# 3-2.net
KiCad netlist of a schematic drawn in Altium Designer
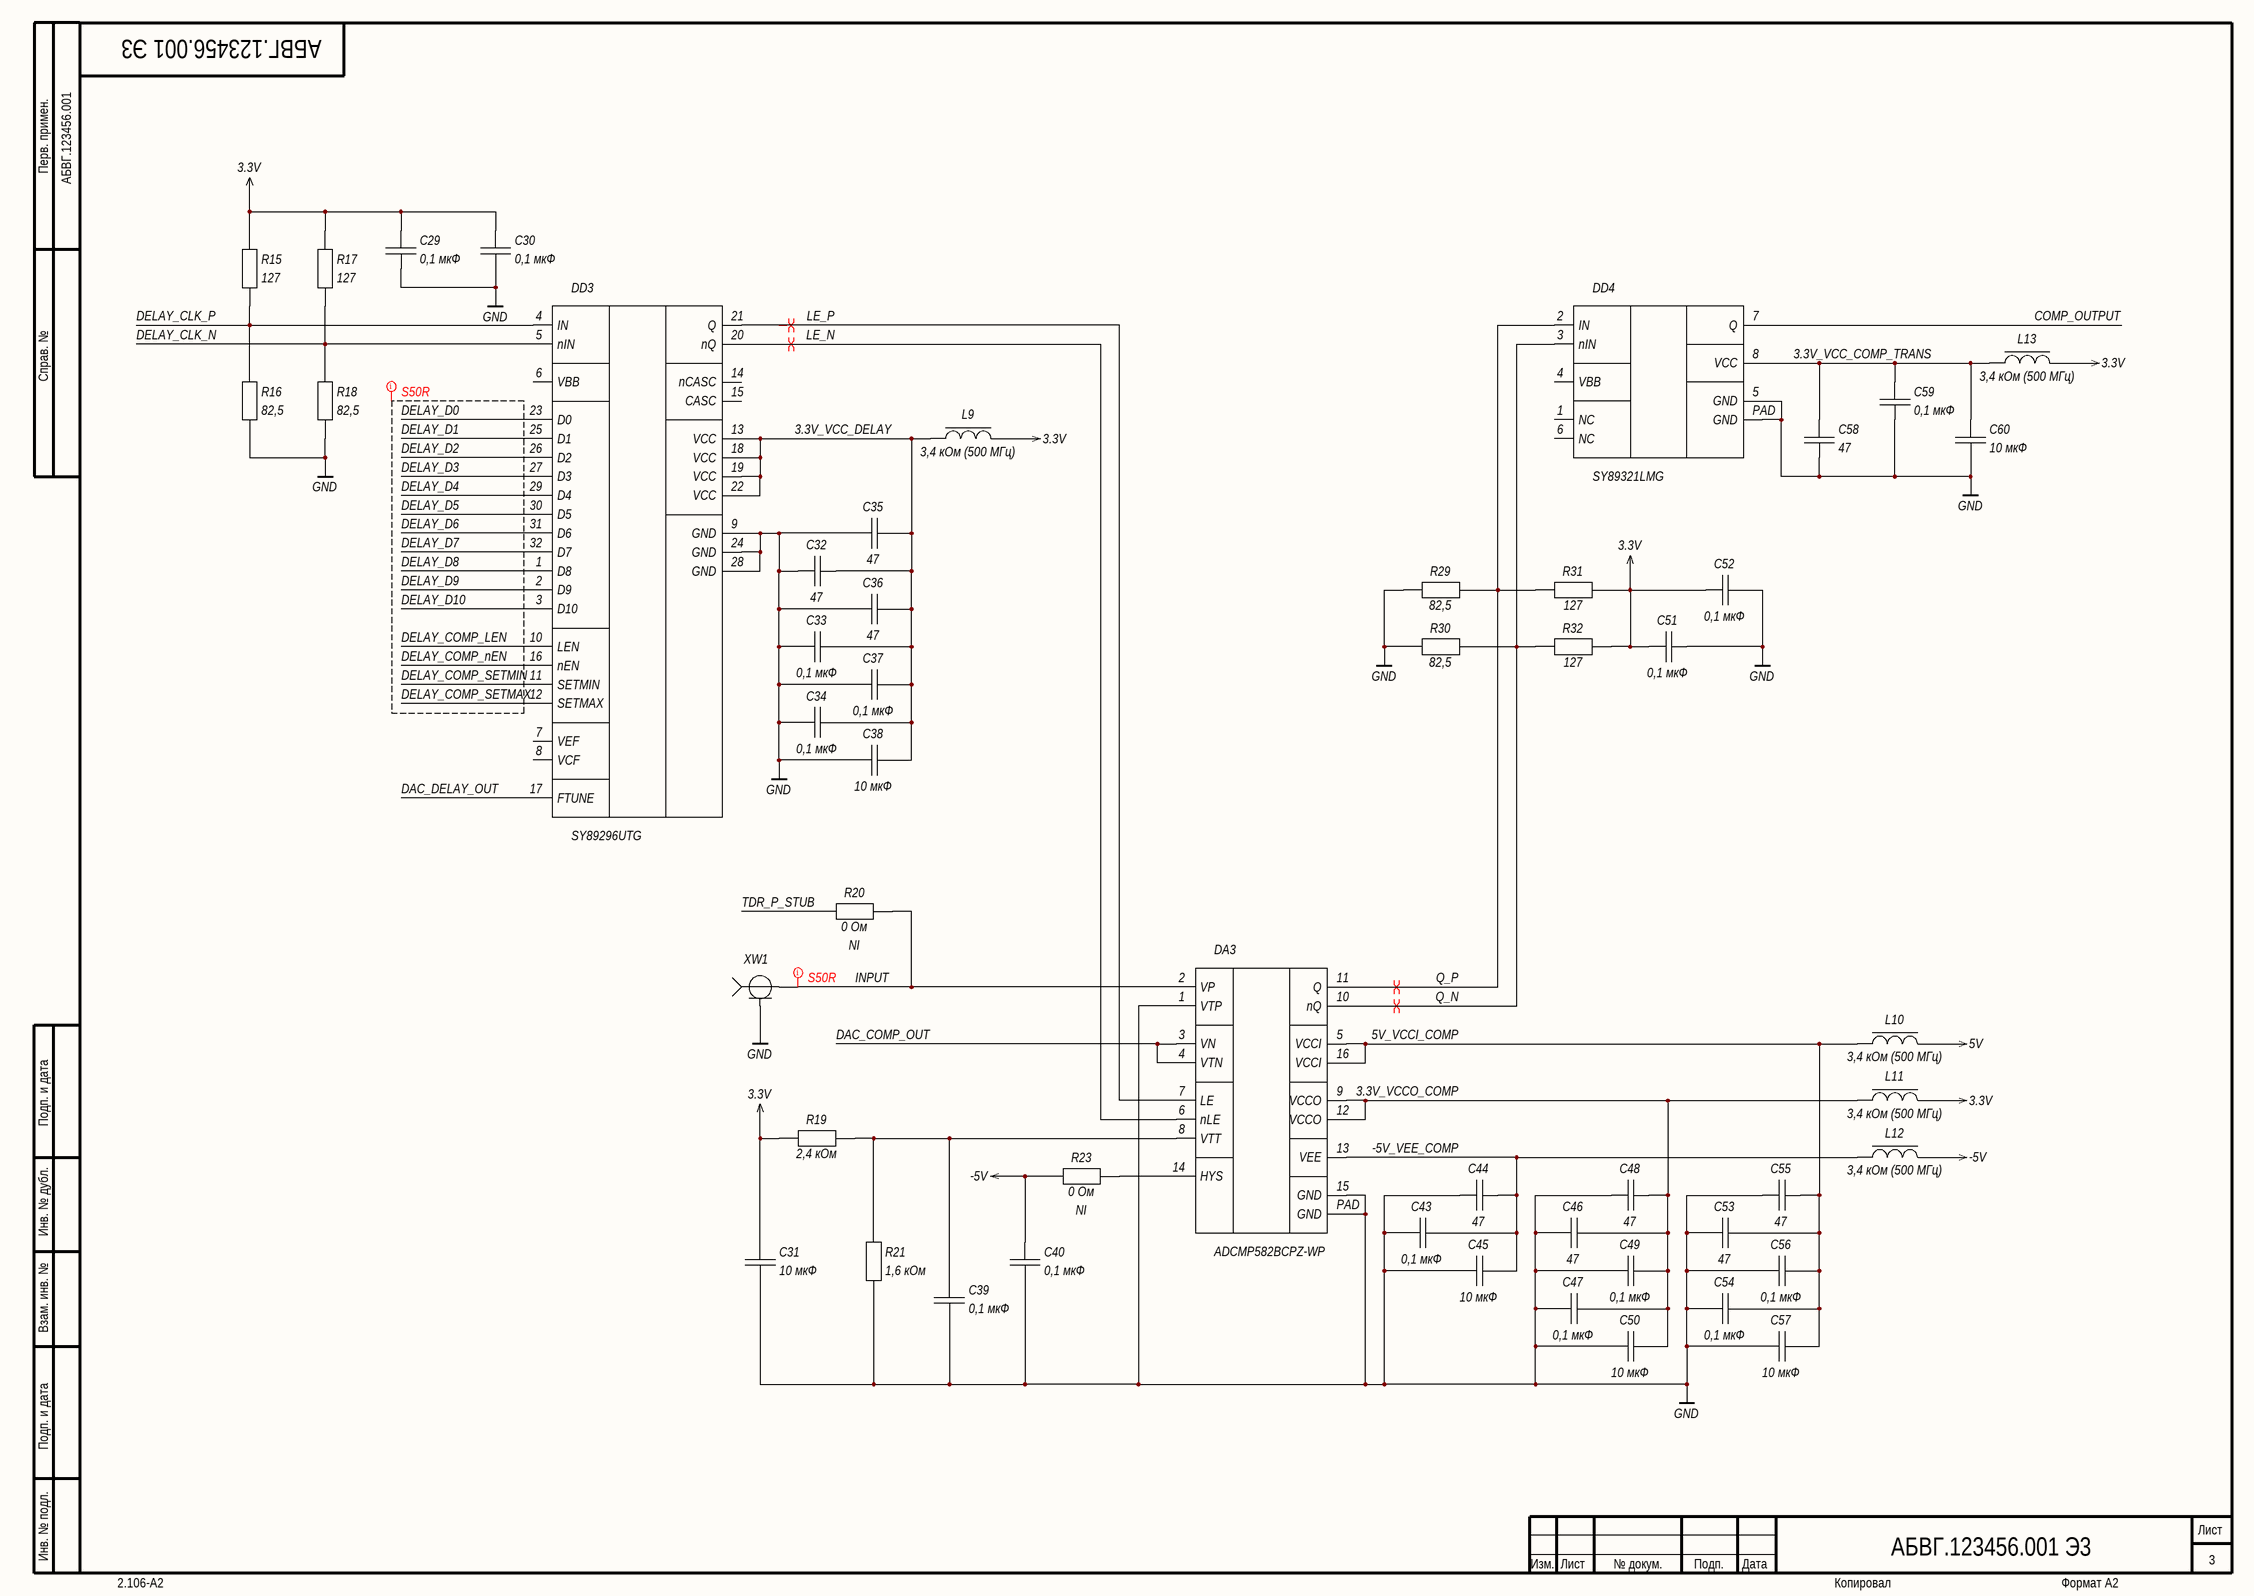
[diagram p0: Э3-2 УВ Компаратор.SchDoc]

(export (version "E")
  (design (tool "Eeschema 10.0.6"))
  (components
    (comp (ref "C29")
      (value "0,1 мкФ")
      (footprint "C0402-B-0.5mm")
      (description "0402 X7R 0,1 мкФ ±10 % 50 В")
      (fields (field (name "PARTNUMBER") "GRM155R71H104KE14D"))
      (libsource (lib "Capacitors") (part "Non Polar Ver."))
    )
    (comp (ref "C30")
      (value "0,1 мкФ")
      (footprint "C0402-B-0.5mm")
      (description "0402 X7R 0,1 мкФ ±10 % 50 В")
      (fields (field (name "PARTNUMBER") "GRM155R71H104KE14D"))
      (libsource (lib "Capacitors") (part "Non Polar Ver."))
    )
    (comp (ref "C31")
      (value "10 мкФ")
      (footprint "C0603-B-0.8mm")
      (description "0603 X5R 10 мкФ ±20 % 25 В")
      (fields (field (name "PARTNUMBER") "GRM188R61E106MA73"))
      (libsource (lib "Capacitors") (part "Non Polar Ver."))
    )
    (comp (ref "C32")
      (value "47")
      (footprint "C0402-B-0.5mm")
      (description "0402 NP0 47 пФ ±5 % 50 В")
      (fields (field (name "PARTNUMBER") "GCM1555C1H470JA16"))
      (libsource (lib "Capacitors") (part "Non Polar Hor."))
    )
    (comp (ref "C33")
      (value "0,1 мкФ")
      (footprint "C0402-B-0.5mm")
      (description "0402 X7R 0,1 мкФ ±10 % 50 В")
      (fields (field (name "PARTNUMBER") "GRM155R71H104KE14D"))
      (libsource (lib "Capacitors") (part "Non Polar Hor."))
    )
    (comp (ref "C34")
      (value "0,1 мкФ")
      (footprint "C0402-B-0.5mm")
      (description "0402 X7R 0,1 мкФ ±10 % 50 В")
      (fields (field (name "PARTNUMBER") "GRM155R71H104KE14D"))
      (libsource (lib "Capacitors") (part "Non Polar Hor."))
    )
    (comp (ref "C35")
      (value "47")
      (footprint "C0402-B-0.5mm")
      (description "0402 NP0 47 пФ ±5 % 50 В")
      (fields (field (name "PARTNUMBER") "GCM1555C1H470JA16"))
      (libsource (lib "Capacitors") (part "Non Polar Hor."))
    )
    (comp (ref "C36")
      (value "47")
      (footprint "C0402-B-0.5mm")
      (description "0402 NP0 47 пФ ±5 % 50 В")
      (fields (field (name "PARTNUMBER") "GCM1555C1H470JA16"))
      (libsource (lib "Capacitors") (part "Non Polar Hor."))
    )
    (comp (ref "C37")
      (value "0,1 мкФ")
      (footprint "C0402-B-0.5mm")
      (description "0402 X7R 0,1 мкФ ±10 % 50 В")
      (fields (field (name "PARTNUMBER") "GRM155R71H104KE14D"))
      (libsource (lib "Capacitors") (part "Non Polar Hor."))
    )
    (comp (ref "C38")
      (value "10 мкФ")
      (footprint "C0603-B-0.8mm")
      (description "0603 X5R 10 мкФ ±20 % 25 В")
      (fields (field (name "PARTNUMBER") "GRM188R61E106MA73"))
      (libsource (lib "Capacitors") (part "Non Polar Hor."))
    )
    (comp (ref "C39")
      (value "0,1 мкФ")
      (footprint "C0402-B-0.5mm")
      (description "0402 X7R 0,1 мкФ ±10 % 50 В")
      (fields (field (name "PARTNUMBER") "GRM155R71H104KE14D"))
      (libsource (lib "Capacitors") (part "Non Polar Ver."))
    )
    (comp (ref "C40")
      (value "0,1 мкФ")
      (footprint "C0402-B-0.5mm")
      (description "0402 X7R 0,1 мкФ ±10 % 50 В")
      (fields (field (name "PARTNUMBER") "GRM155R71H104KE14D"))
      (libsource (lib "Capacitors") (part "Non Polar Ver."))
    )
    (comp (ref "C43")
      (value "0,1 мкФ")
      (footprint "C0402-B-0.5mm")
      (description "0402 X7R 0,1 мкФ ±10 % 50 В")
      (fields (field (name "PARTNUMBER") "GRM155R71H104KE14D"))
      (libsource (lib "Capacitors") (part "Non Polar Hor."))
    )
    (comp (ref "C44")
      (value "47")
      (footprint "C0402-B-0.5mm")
      (description "0402 NP0 47 пФ ±5 % 50 В")
      (fields (field (name "PARTNUMBER") "GCM1555C1H470JA16"))
      (libsource (lib "Capacitors") (part "Non Polar Hor."))
    )
    (comp (ref "C45")
      (value "10 мкФ")
      (footprint "C0603-B-0.8mm")
      (description "0603 X5R 10 мкФ ±20 % 25 В")
      (fields (field (name "PARTNUMBER") "GRM188R61E106MA73"))
      (libsource (lib "Capacitors") (part "Non Polar Hor."))
    )
    (comp (ref "C46")
      (value "47")
      (footprint "C0402-B-0.5mm")
      (description "0402 NP0 47 пФ ±5 % 50 В")
      (fields (field (name "PARTNUMBER") "GCM1555C1H470JA16"))
      (libsource (lib "Capacitors") (part "Non Polar Hor."))
    )
    (comp (ref "C47")
      (value "0,1 мкФ")
      (footprint "C0402-B-0.5mm")
      (description "0402 X7R 0,1 мкФ ±10 % 50 В")
      (fields (field (name "PARTNUMBER") "GRM155R71H104KE14D"))
      (libsource (lib "Capacitors") (part "Non Polar Hor."))
    )
    (comp (ref "C48")
      (value "47")
      (footprint "C0402-B-0.5mm")
      (description "0402 NP0 47 пФ ±5 % 50 В")
      (fields (field (name "PARTNUMBER") "GCM1555C1H470JA16"))
      (libsource (lib "Capacitors") (part "Non Polar Hor."))
    )
    (comp (ref "C49")
      (value "0,1 мкФ")
      (footprint "C0402-B-0.5mm")
      (description "0402 X7R 0,1 мкФ ±10 % 50 В")
      (fields (field (name "PARTNUMBER") "GRM155R71H104KE14D"))
      (libsource (lib "Capacitors") (part "Non Polar Hor."))
    )
    (comp (ref "C50")
      (value "10 мкФ")
      (footprint "C0603-B-0.8mm")
      (description "0603 X5R 10 мкФ ±20 % 25 В")
      (fields (field (name "PARTNUMBER") "GRM188R61E106MA73"))
      (libsource (lib "Capacitors") (part "Non Polar Hor."))
    )
    (comp (ref "C51")
      (value "0,1 мкФ")
      (footprint "C0402-B-0.5mm")
      (description "0402 X7R 0,1 мкФ ±10 % 50 В")
      (fields (field (name "PARTNUMBER") "GRM155R71H104KE14D"))
      (libsource (lib "Capacitors") (part "Non Polar Hor."))
    )
    (comp (ref "C52")
      (value "0,1 мкФ")
      (footprint "C0402-B-0.5mm")
      (description "0402 X7R 0,1 мкФ ±10 % 50 В")
      (fields (field (name "PARTNUMBER") "GRM155R71H104KE14D"))
      (libsource (lib "Capacitors") (part "Non Polar Hor."))
    )
    (comp (ref "C53")
      (value "47")
      (footprint "C0402-B-0.5mm")
      (description "0402 NP0 47 пФ ±5 % 50 В")
      (fields (field (name "PARTNUMBER") "GCM1555C1H470JA16"))
      (libsource (lib "Capacitors") (part "Non Polar Hor."))
    )
    (comp (ref "C54")
      (value "0,1 мкФ")
      (footprint "C0402-B-0.5mm")
      (description "0402 X7R 0,1 мкФ ±10 % 50 В")
      (fields (field (name "PARTNUMBER") "GRM155R71H104KE14D"))
      (libsource (lib "Capacitors") (part "Non Polar Hor."))
    )
    (comp (ref "C55")
      (value "47")
      (footprint "C0402-B-0.5mm")
      (description "0402 NP0 47 пФ ±5 % 50 В")
      (fields (field (name "PARTNUMBER") "GCM1555C1H470JA16"))
      (libsource (lib "Capacitors") (part "Non Polar Hor."))
    )
    (comp (ref "C56")
      (value "0,1 мкФ")
      (footprint "C0402-B-0.5mm")
      (description "0402 X7R 0,1 мкФ ±10 % 50 В")
      (fields (field (name "PARTNUMBER") "GRM155R71H104KE14D"))
      (libsource (lib "Capacitors") (part "Non Polar Hor."))
    )
    (comp (ref "C57")
      (value "10 мкФ")
      (footprint "C0603-B-0.8mm")
      (description "0603 X5R 10 мкФ ±20 % 25 В")
      (fields (field (name "PARTNUMBER") "GRM188R61E106MA73"))
      (libsource (lib "Capacitors") (part "Non Polar Hor."))
    )
    (comp (ref "C58")
      (value "47")
      (footprint "C0402-B-0.5mm")
      (description "0402 NP0 47 пФ ±5 % 50 В")
      (fields (field (name "PARTNUMBER") "GCM1555C1H470JA16"))
      (libsource (lib "Capacitors") (part "Non Polar Ver."))
    )
    (comp (ref "C59")
      (value "0,1 мкФ")
      (footprint "C0402-B-0.5mm")
      (description "0402 X7R 0,1 мкФ ±10 % 50 В")
      (fields (field (name "PARTNUMBER") "GRM155R71H104KE14D"))
      (libsource (lib "Capacitors") (part "Non Polar Ver."))
    )
    (comp (ref "C60")
      (value "10 мкФ")
      (footprint "C0603-B-0.8mm")
      (description "0603 X5R 10 мкФ ±20 % 25 В")
      (fields (field (name "PARTNUMBER") "GRM188R61E106MA73"))
      (libsource (lib "Capacitors") (part "Non Polar Ver."))
    )
    (comp (ref "DA3")
      (value "ADCMP582BCPZ-WP")
      (footprint "16-LFCSP-3-H0.75")
      (description "Ultrafast SiGe Voltage Comparators")
      (fields (field (name "MANUFACTURER") "Analog Devices, Inc."))
      (libsource (lib "Analog") (part "ADCMP582"))
    )
    (comp (ref "DD3")
      (value "SY89296UTG")
      (footprint "32-TQFP-B")
      (description "2.5V/3.3V, 1.5 GHz, LVPECL Programmable Delay with Fine Tune Control")
      (fields (field (name "MANUFACTURER") "Microchip"))
      (libsource (lib "Digital") (part "SY89296UTG"))
    )
    (comp (ref "DD4")
      (value "SY89321LMG")
      (footprint "8-MLF")
      (description "3.3V DIFFERENTIAL LVPECL/CML/LVDS-to-LVTTL TRANSLATOR")
      (fields (field (name "MANUFACTURER") "Microchip Technology"))
      (libsource (lib "Digital") (part "SY89321L"))
    )
    (comp (ref "L9")
      (value "3,4 кОм (500 МГц)")
      (footprint "L0402-B-0.5mm")
      (fields (field (name "PARTNUMBER") "BLM15HD182BH1"))
      (libsource (lib "Inductors") (part "Inductor MC Hor."))
    )
    (comp (ref "L10")
      (value "3,4 кОм (500 МГц)")
      (footprint "L0402-B-0.5mm")
      (fields (field (name "PARTNUMBER") "BLM15HD182BH1"))
      (libsource (lib "Inductors") (part "Inductor MC Hor."))
    )
    (comp (ref "L11")
      (value "3,4 кОм (500 МГц)")
      (footprint "L0402-B-0.5mm")
      (fields (field (name "PARTNUMBER") "BLM15HD182BH1"))
      (libsource (lib "Inductors") (part "Inductor MC Hor."))
    )
    (comp (ref "L12")
      (value "3,4 кОм (500 МГц)")
      (footprint "L0402-B-0.5mm")
      (fields (field (name "PARTNUMBER") "BLM15HD182BH1"))
      (libsource (lib "Inductors") (part "Inductor MC Hor."))
    )
    (comp (ref "L13")
      (value "3,4 кОм (500 МГц)")
      (footprint "L0402-B-0.5mm")
      (fields (field (name "PARTNUMBER") "BLM15HD182BH1"))
      (libsource (lib "Inductors") (part "Inductor MC Hor."))
    )
    (comp (ref "R15")
      (value "127")
      (footprint "CR0402-B-0.35mm")
      (description "0402 127 Ом ±1 %")
      (libsource (lib "Resistors") (part "Resistor Ver."))
    )
    (comp (ref "R16")
      (value "82,5")
      (footprint "CR0402-B-0.35mm")
      (description "0402 82,5 Ом ±1 %")
      (libsource (lib "Resistors") (part "Resistor Ver."))
    )
    (comp (ref "R17")
      (value "127")
      (footprint "CR0402-B-0.35mm")
      (description "0402 127 Ом ±1 %")
      (libsource (lib "Resistors") (part "Resistor Ver."))
    )
    (comp (ref "R18")
      (value "82,5")
      (footprint "CR0402-B-0.35mm")
      (description "0402 82,5 Ом ±1 %")
      (libsource (lib "Resistors") (part "Resistor Ver."))
    )
    (comp (ref "R19")
      (value "2,4 кОм")
      (footprint "CR0402-B-0.35mm")
      (description "0402 2,4 кОм ±1 %")
      (libsource (lib "Resistors") (part "Resistor Hor."))
    )
    (comp (ref "R20")
      (value "0 Ом")
      (footprint "CR0402-B-0.35mm")
      (description "0402 0 Ом")
      (fields (field (name "COMPONENTTYPE") "NI"))
      (libsource (lib "") (part "Resistor Hor._1"))
    )
    (comp (ref "R21")
      (value "1,6 кОм")
      (footprint "CR0402-B-0.35mm")
      (description "0402 1,6 кОм ±1 %")
      (libsource (lib "Resistors") (part "Resistor Ver."))
    )
    (comp (ref "R23")
      (value "0 Ом")
      (footprint "CR0402-B-0.35mm")
      (description "0402 0 Ом")
      (fields (field (name "COMPONENTTYPE") "NI"))
      (libsource (lib "Resistors") (part "Resistor Hor."))
    )
    (comp (ref "R29")
      (value "82,5")
      (footprint "CR0402-B-0.35mm")
      (description "0402 82,5 Ом ±1 %")
      (libsource (lib "Resistors") (part "Resistor Hor."))
    )
    (comp (ref "R30")
      (value "82,5")
      (footprint "CR0402-B-0.35mm")
      (description "0402 82,5 Ом ±1 %")
      (libsource (lib "Resistors") (part "Resistor Hor."))
    )
    (comp (ref "R31")
      (value "127")
      (footprint "CR0402-B-0.35mm")
      (description "0402 127 Ом ±1 %")
      (libsource (lib "Resistors") (part "Resistor Hor."))
    )
    (comp (ref "R32")
      (value "127")
      (footprint "CR0402-B-0.35mm")
      (description "0402 127 Ом ±1 %")
      (libsource (lib "Resistors") (part "Resistor Hor."))
    )
    (comp (ref "XW1")
      (value "XW(S)")
      (footprint "SMA-J-P-H-ST-EM1")
      (libsource (lib "Connectors") (part "XW(S)"))
    )
  )
  (nets
    (net (code "1") (name "-5V") (class "Default")
      (node (ref "C40") (pin "1") (pinfunction "1_1") (pintype "passive"))
      (node (ref "L12") (pin "2") (pinfunction "2_2") (pintype "passive"))
      (node (ref "R23") (pin "1") (pinfunction "1_1") (pintype "passive"))
    )
    (net (code "2") (name "/-5V_VEE_COMP") (class "Default")
      (node (ref "C43") (pin "2") (pinfunction "2_2") (pintype "passive"))
      (node (ref "C44") (pin "2") (pinfunction "2_2") (pintype "passive"))
      (node (ref "C45") (pin "2") (pinfunction "2_2") (pintype "passive"))
      (node (ref "DA3") (pin "13") (pinfunction "VEE_13") (pintype "passive"))
      (node (ref "L12") (pin "1") (pinfunction "1_1") (pintype "passive"))
    )
    (net (code "3") (name "/3.3V_VCCO_COMP") (class "Default")
      (node (ref "C46") (pin "2") (pinfunction "2_2") (pintype "passive"))
      (node (ref "C47") (pin "2") (pinfunction "2_2") (pintype "passive"))
      (node (ref "C48") (pin "2") (pinfunction "2_2") (pintype "passive"))
      (node (ref "C49") (pin "2") (pinfunction "2_2") (pintype "passive"))
      (node (ref "C50") (pin "2") (pinfunction "2_2") (pintype "passive"))
      (node (ref "DA3") (pin "12") (pinfunction "VCCO_12") (pintype "passive"))
      (node (ref "DA3") (pin "9") (pinfunction "VCCO_9") (pintype "passive"))
      (node (ref "L11") (pin "1") (pinfunction "1_1") (pintype "passive"))
    )
    (net (code "4") (name "/3.3V_VCC_COMP_TRANS") (class "Default")
      (node (ref "C58") (pin "1") (pinfunction "1_1") (pintype "passive"))
      (node (ref "C59") (pin "1") (pinfunction "1_1") (pintype "passive"))
      (node (ref "C60") (pin "1") (pinfunction "1_1") (pintype "passive"))
      (node (ref "DD4") (pin "8") (pinfunction "VCC_8") (pintype "passive"))
      (node (ref "L13") (pin "1") (pinfunction "1_1") (pintype "passive"))
    )
    (net (code "5") (name "/3.3V_VCC_DELAY") (class "Default")
      (node (ref "C32") (pin "2") (pinfunction "2_2") (pintype "passive"))
      (node (ref "C33") (pin "2") (pinfunction "2_2") (pintype "passive"))
      (node (ref "C34") (pin "2") (pinfunction "2_2") (pintype "passive"))
      (node (ref "C35") (pin "2") (pinfunction "2_2") (pintype "passive"))
      (node (ref "C36") (pin "2") (pinfunction "2_2") (pintype "passive"))
      (node (ref "C37") (pin "2") (pinfunction "2_2") (pintype "passive"))
      (node (ref "C38") (pin "2") (pinfunction "2_2") (pintype "passive"))
      (node (ref "DD3") (pin "13") (pinfunction "VCC_13") (pintype "passive"))
      (node (ref "DD3") (pin "18") (pinfunction "VCC_18") (pintype "passive"))
      (node (ref "DD3") (pin "19") (pinfunction "VCC_19") (pintype "passive"))
      (node (ref "DD3") (pin "22") (pinfunction "VCC_22") (pintype "passive"))
      (node (ref "L9") (pin "1") (pinfunction "1_1") (pintype "passive"))
    )
    (net (code "6") (name "/5V_VCCI_COMP") (class "Default")
      (node (ref "C53") (pin "2") (pinfunction "2_2") (pintype "passive"))
      (node (ref "C54") (pin "2") (pinfunction "2_2") (pintype "passive"))
      (node (ref "C55") (pin "2") (pinfunction "2_2") (pintype "passive"))
      (node (ref "C56") (pin "2") (pinfunction "2_2") (pintype "passive"))
      (node (ref "C57") (pin "2") (pinfunction "2_2") (pintype "passive"))
      (node (ref "DA3") (pin "16") (pinfunction "VCCI_16") (pintype "passive"))
      (node (ref "DA3") (pin "5") (pinfunction "VCCI_5") (pintype "passive"))
      (node (ref "L10") (pin "1") (pinfunction "1_1") (pintype "passive"))
    )
    (net (code "7") (name "/COMP_OUTPUT") (class "Default")
      (node (ref "DD4") (pin "7") (pinfunction "Q_7") (pintype "passive"))
    )
    (net (code "8") (name "/DAC_COMP_OUT") (class "Default")
      (node (ref "DA3") (pin "3") (pinfunction "VN_3") (pintype "passive"))
      (node (ref "DA3") (pin "4") (pinfunction "VTN_4") (pintype "passive"))
    )
    (net (code "9") (name "/DAC_DELAY_OUT") (class "Default")
      (node (ref "DD3") (pin "17") (pinfunction "FTUNE_17") (pintype "passive"))
    )
    (net (code "10") (name "/DELAY_CLK_N") (class "Default")
      (node (ref "DD3") (pin "5") (pinfunction "nIN_5") (pintype "passive"))
      (node (ref "R17") (pin "2") (pinfunction "2_2") (pintype "passive"))
      (node (ref "R18") (pin "1") (pinfunction "1_1") (pintype "passive"))
    )
    (net (code "11") (name "/DELAY_CLK_P") (class "Default")
      (node (ref "DD3") (pin "4") (pinfunction "IN_4") (pintype "passive"))
      (node (ref "R15") (pin "2") (pinfunction "2_2") (pintype "passive"))
      (node (ref "R16") (pin "1") (pinfunction "1_1") (pintype "passive"))
    )
    (net (code "12") (name "/DELAY_COMP_LEN") (class "Default")
      (node (ref "DD3") (pin "10") (pinfunction "LEN_10") (pintype "passive"))
    )
    (net (code "13") (name "/DELAY_COMP_SETMAX") (class "Default")
      (node (ref "DD3") (pin "12") (pinfunction "SETMAX_12") (pintype "passive"))
    )
    (net (code "14") (name "/DELAY_COMP_SETMIN") (class "Default")
      (node (ref "DD3") (pin "11") (pinfunction "SETMIN_11") (pintype "passive"))
    )
    (net (code "15") (name "/DELAY_COMP_nEN") (class "Default")
      (node (ref "DD3") (pin "16") (pinfunction "nEN_16") (pintype "passive"))
    )
    (net (code "16") (name "/DELAY_D0") (class "Default")
      (node (ref "DD3") (pin "23") (pinfunction "D0_23") (pintype "passive"))
    )
    (net (code "17") (name "/DELAY_D1") (class "Default")
      (node (ref "DD3") (pin "25") (pinfunction "D1_25") (pintype "passive"))
    )
    (net (code "18") (name "/DELAY_D2") (class "Default")
      (node (ref "DD3") (pin "26") (pinfunction "D2_26") (pintype "passive"))
    )
    (net (code "19") (name "/DELAY_D3") (class "Default")
      (node (ref "DD3") (pin "27") (pinfunction "D3_27") (pintype "passive"))
    )
    (net (code "20") (name "/DELAY_D4") (class "Default")
      (node (ref "DD3") (pin "29") (pinfunction "D4_29") (pintype "passive"))
    )
    (net (code "21") (name "/DELAY_D5") (class "Default")
      (node (ref "DD3") (pin "30") (pinfunction "D5_30") (pintype "passive"))
    )
    (net (code "22") (name "/DELAY_D6") (class "Default")
      (node (ref "DD3") (pin "31") (pinfunction "D6_31") (pintype "passive"))
    )
    (net (code "23") (name "/DELAY_D7") (class "Default")
      (node (ref "DD3") (pin "32") (pinfunction "D7_32") (pintype "passive"))
    )
    (net (code "24") (name "/DELAY_D8") (class "Default")
      (node (ref "DD3") (pin "1") (pinfunction "D8_1") (pintype "passive"))
    )
    (net (code "25") (name "/DELAY_D9") (class "Default")
      (node (ref "DD3") (pin "2") (pinfunction "D9_2") (pintype "passive"))
    )
    (net (code "26") (name "/DELAY_D10") (class "Default")
      (node (ref "DD3") (pin "3") (pinfunction "D10_3") (pintype "passive"))
    )
    (net (code "27") (name "/INPUT") (class "Default")
      (node (ref "DA3") (pin "2") (pinfunction "VP_2") (pintype "passive"))
      (node (ref "R20") (pin "1") (pinfunction "1_1") (pintype "passive"))
      (node (ref "XW1") (pin "1") (pinfunction "1_1") (pintype "passive"))
    )
    (net (code "28") (name "/LE_N") (class "Default")
      (node (ref "DA3") (pin "6") (pinfunction "nLE_6") (pintype "passive"))
      (node (ref "DD3") (pin "20") (pinfunction "nQ_20") (pintype "passive"))
    )
    (net (code "29") (name "/LE_P") (class "Default")
      (node (ref "DA3") (pin "7") (pinfunction "LE_7") (pintype "passive"))
      (node (ref "DD3") (pin "21") (pinfunction "Q_21") (pintype "passive"))
    )
    (net (code "30") (name "/Q_N") (class "Default")
      (node (ref "DA3") (pin "10") (pinfunction "nQ_10") (pintype "passive"))
      (node (ref "DD4") (pin "3") (pinfunction "nIN_3") (pintype "passive"))
      (node (ref "R30") (pin "2") (pinfunction "2_2") (pintype "passive"))
      (node (ref "R32") (pin "1") (pinfunction "1_1") (pintype "passive"))
    )
    (net (code "31") (name "/Q_P") (class "Default")
      (node (ref "DA3") (pin "11") (pinfunction "Q_11") (pintype "passive"))
      (node (ref "DD4") (pin "2") (pinfunction "IN_2") (pintype "passive"))
      (node (ref "R29") (pin "2") (pinfunction "2_2") (pintype "passive"))
      (node (ref "R31") (pin "1") (pinfunction "1_1") (pintype "passive"))
    )
    (net (code "32") (name "/TDR_P_STUB") (class "Default")
      (node (ref "R20") (pin "2") (pinfunction "2_2") (pintype "passive"))
    )
    (net (code "33") (name "3.3V") (class "Default")
      (node (ref "C29") (pin "1") (pinfunction "1_1") (pintype "passive"))
      (node (ref "C30") (pin "1") (pinfunction "1_1") (pintype "passive"))
      (node (ref "C31") (pin "1") (pinfunction "1_1") (pintype "passive"))
      (node (ref "C51") (pin "1") (pinfunction "1_1") (pintype "passive"))
      (node (ref "C52") (pin "1") (pinfunction "1_1") (pintype "passive"))
      (node (ref "L11") (pin "2") (pinfunction "2_2") (pintype "passive"))
      (node (ref "L13") (pin "2") (pinfunction "2_2") (pintype "passive"))
      (node (ref "L9") (pin "2") (pinfunction "2_2") (pintype "passive"))
      (node (ref "R15") (pin "1") (pinfunction "1_1") (pintype "passive"))
      (node (ref "R17") (pin "1") (pinfunction "1_1") (pintype "passive"))
      (node (ref "R19") (pin "1") (pinfunction "1_1") (pintype "passive"))
      (node (ref "R31") (pin "2") (pinfunction "2_2") (pintype "passive"))
      (node (ref "R32") (pin "2") (pinfunction "2_2") (pintype "passive"))
    )
    (net (code "34") (name "5V") (class "Default")
      (node (ref "L10") (pin "2") (pinfunction "2_2") (pintype "passive"))
    )
    (net (code "35") (name "GND") (class "Default")
      (node (ref "C29") (pin "2") (pinfunction "2_2") (pintype "passive"))
      (node (ref "C30") (pin "2") (pinfunction "2_2") (pintype "passive"))
      (node (ref "C31") (pin "2") (pinfunction "2_2") (pintype "passive"))
      (node (ref "C32") (pin "1") (pinfunction "1_1") (pintype "passive"))
      (node (ref "C33") (pin "1") (pinfunction "1_1") (pintype "passive"))
      (node (ref "C34") (pin "1") (pinfunction "1_1") (pintype "passive"))
      (node (ref "C35") (pin "1") (pinfunction "1_1") (pintype "passive"))
      (node (ref "C36") (pin "1") (pinfunction "1_1") (pintype "passive"))
      (node (ref "C37") (pin "1") (pinfunction "1_1") (pintype "passive"))
      (node (ref "C38") (pin "1") (pinfunction "1_1") (pintype "passive"))
      (node (ref "C39") (pin "2") (pinfunction "2_2") (pintype "passive"))
      (node (ref "C40") (pin "2") (pinfunction "2_2") (pintype "passive"))
      (node (ref "C43") (pin "1") (pinfunction "1_1") (pintype "passive"))
      (node (ref "C44") (pin "1") (pinfunction "1_1") (pintype "passive"))
      (node (ref "C45") (pin "1") (pinfunction "1_1") (pintype "passive"))
      (node (ref "C46") (pin "1") (pinfunction "1_1") (pintype "passive"))
      (node (ref "C47") (pin "1") (pinfunction "1_1") (pintype "passive"))
      (node (ref "C48") (pin "1") (pinfunction "1_1") (pintype "passive"))
      (node (ref "C49") (pin "1") (pinfunction "1_1") (pintype "passive"))
      (node (ref "C50") (pin "1") (pinfunction "1_1") (pintype "passive"))
      (node (ref "C51") (pin "2") (pinfunction "2_2") (pintype "passive"))
      (node (ref "C52") (pin "2") (pinfunction "2_2") (pintype "passive"))
      (node (ref "C53") (pin "1") (pinfunction "1_1") (pintype "passive"))
      (node (ref "C54") (pin "1") (pinfunction "1_1") (pintype "passive"))
      (node (ref "C55") (pin "1") (pinfunction "1_1") (pintype "passive"))
      (node (ref "C56") (pin "1") (pinfunction "1_1") (pintype "passive"))
      (node (ref "C57") (pin "1") (pinfunction "1_1") (pintype "passive"))
      (node (ref "C58") (pin "2") (pinfunction "2_2") (pintype "passive"))
      (node (ref "C59") (pin "2") (pinfunction "2_2") (pintype "passive"))
      (node (ref "C60") (pin "2") (pinfunction "2_2") (pintype "passive"))
      (node (ref "DA3") (pin "1") (pinfunction "VTP_1") (pintype "passive"))
      (node (ref "DA3") (pin "15") (pinfunction "GND_15") (pintype "passive"))
      (node (ref "DA3") (pin "PAD") (pinfunction "GND_PAD") (pintype "passive"))
      (node (ref "DD3") (pin "24") (pinfunction "GND_24") (pintype "passive"))
      (node (ref "DD3") (pin "28") (pinfunction "GND_28") (pintype "passive"))
      (node (ref "DD3") (pin "9") (pinfunction "GND_9") (pintype "passive"))
      (node (ref "DD4") (pin "5") (pinfunction "GND_5") (pintype "passive"))
      (node (ref "DD4") (pin "PAD") (pinfunction "GND_PAD") (pintype "passive"))
      (node (ref "R16") (pin "2") (pinfunction "2_2") (pintype "passive"))
      (node (ref "R18") (pin "2") (pinfunction "2_2") (pintype "passive"))
      (node (ref "R21") (pin "2") (pinfunction "2_2") (pintype "passive"))
      (node (ref "R29") (pin "1") (pinfunction "1_1") (pintype "passive"))
      (node (ref "R30") (pin "1") (pinfunction "1_1") (pintype "passive"))
      (node (ref "XW1") (pin "2") (pinfunction "2_2") (pintype "passive"))
    )
    (net (code "36") (name "Net-(DA3-HYS)") (class "Default")
      (node (ref "DA3") (pin "14") (pinfunction "HYS_14") (pintype "passive"))
      (node (ref "R23") (pin "2") (pinfunction "2_2") (pintype "passive"))
    )
    (net (code "37") (name "Net-(DA3-VTT)") (class "Default")
      (node (ref "C39") (pin "1") (pinfunction "1_1") (pintype "passive"))
      (node (ref "DA3") (pin "8") (pinfunction "VTT_8") (pintype "passive"))
      (node (ref "R19") (pin "2") (pinfunction "2_2") (pintype "passive"))
      (node (ref "R21") (pin "1") (pinfunction "1_1") (pintype "passive"))
    )
    (net (code "38") (name "unconnected-(DD3-CASC-Pad15)") (class "Default")
      (node (ref "DD3") (pin "15") (pinfunction "CASC_15") (pintype "passive"))
    )
    (net (code "39") (name "unconnected-(DD3-VBB-Pad6)") (class "Default")
      (node (ref "DD3") (pin "6") (pinfunction "VBB_6") (pintype "passive"))
    )
    (net (code "40") (name "unconnected-(DD3-VCF-Pad8)") (class "Default")
      (node (ref "DD3") (pin "8") (pinfunction "VCF_8") (pintype "passive"))
    )
    (net (code "41") (name "unconnected-(DD3-VEF-Pad7)") (class "Default")
      (node (ref "DD3") (pin "7") (pinfunction "VEF_7") (pintype "passive"))
    )
    (net (code "42") (name "unconnected-(DD3-nCASC-Pad14)") (class "Default")
      (node (ref "DD3") (pin "14") (pinfunction "nCASC_14") (pintype "passive"))
    )
    (net (code "43") (name "unconnected-(DD4-NC-Pad1)") (class "Default")
      (node (ref "DD4") (pin "1") (pinfunction "NC_1") (pintype "passive"))
    )
    (net (code "44") (name "unconnected-(DD4-NC-Pad6)") (class "Default")
      (node (ref "DD4") (pin "6") (pinfunction "NC_6") (pintype "passive"))
    )
    (net (code "45") (name "unconnected-(DD4-VBB-Pad4)") (class "Default")
      (node (ref "DD4") (pin "4") (pinfunction "VBB_4") (pintype "passive"))
    )
  )
)
